# MCU_-_IMU.net
KiCad netlist of a schematic drawn in Altium Designer
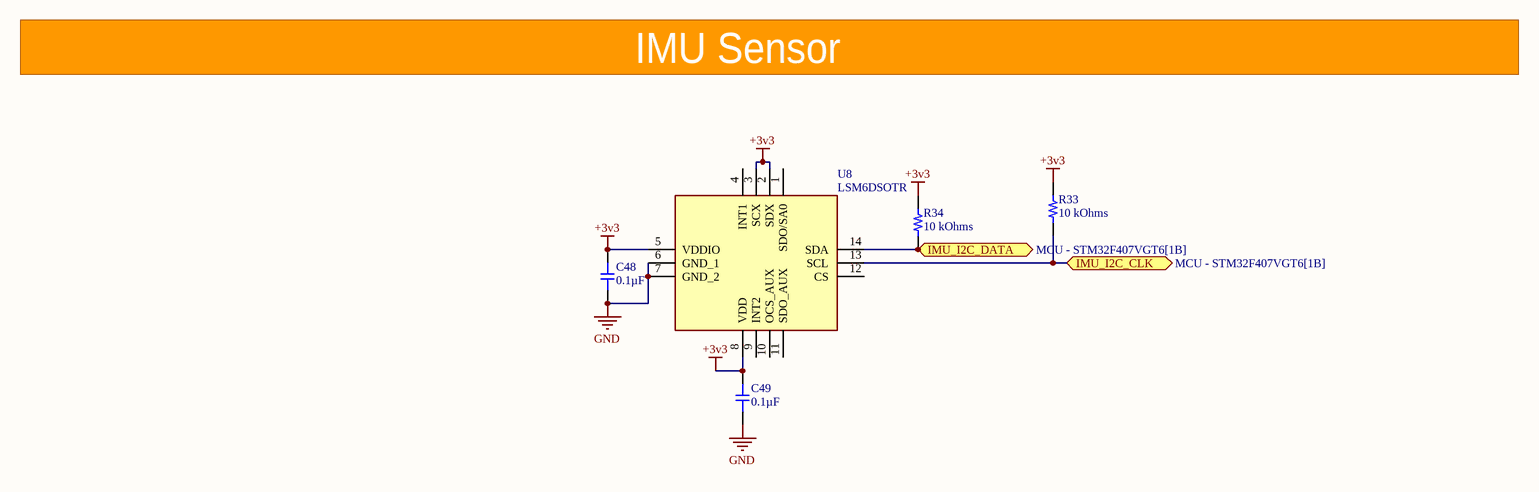
[diagram p0: MCU - IMU.SchDoc]

(export (version "E")
  (design (tool "Eeschema 10.0.6"))
  (components
    (comp (ref "C48")
      (value "0.1µF")
      (footprint "0603_Footprint")
      (description "0.1uF 0603 Surface Capacitor")
      (libsource (lib "ELK_H7-V2 Library") (part "0.1uF 0603 Surface Capacitor_1_1_1_1_1_1"))
    )
    (comp (ref "C49")
      (value "0.1µF")
      (footprint "0603_Footprint")
      (description "0.1uF 0603 Surface Capacitor")
      (libsource (lib "ELK_H7-V2 Library") (part "0.1uF 0603 Surface Capacitor_1_1_1_1_1_1"))
    )
    (comp (ref "R33")
      (value "10 kOhms")
      (footprint "0603_RES")
      (description "10 kOhms 0603")
      (libsource (lib "ELK_H7-V2 Library") (part "10 kOhms 0603"))
    )
    (comp (ref "R34")
      (value "10 kOhms")
      (footprint "0603_RES")
      (description "10 kOhms 0603")
      (libsource (lib "ELK_H7-V2 Library") (part "10 kOhms 0603"))
    )
    (comp (ref "U8")
      (value "LSM6DSOTR")
      (footprint "LGA-14(2.5X3X0.86)")
      (description "Accelerometer")
      (fields (field (name "MOUSER PART NUMBER") "511-LSM6DSOTR"))
      (libsource (lib "ELK_H7-V2 Library") (part "LSM6DSOTR"))
    )
  )
  (nets
    (net (code "1") (name "+3v3") (class "Default")
      (node (ref "C48") (pin "1") (pinfunction "1_1") (pintype "passive"))
      (node (ref "C49") (pin "1") (pinfunction "1_1") (pintype "passive"))
      (node (ref "R33") (pin "1") (pinfunction "1_1") (pintype "passive"))
      (node (ref "R34") (pin "2") (pinfunction "2_2") (pintype "passive"))
      (node (ref "U8") (pin "2") (pinfunction "SDX_2") (pintype "passive"))
      (node (ref "U8") (pin "3") (pinfunction "SCX_3") (pintype "passive"))
      (node (ref "U8") (pin "5") (pinfunction "VDDIO_5") (pintype "passive"))
      (node (ref "U8") (pin "8") (pinfunction "VDD_8") (pintype "passive"))
    )
    (net (code "2") (name "/IMU_I2C_CLK") (class "Default")
      (node (ref "R33") (pin "2") (pinfunction "2_2") (pintype "passive"))
      (node (ref "U8") (pin "13") (pinfunction "SCL_13") (pintype "passive"))
    )
    (net (code "3") (name "/IMU_I2C_DATA") (class "Default")
      (node (ref "R34") (pin "1") (pinfunction "1_1") (pintype "passive"))
      (node (ref "U8") (pin "14") (pinfunction "SDA_14") (pintype "passive"))
    )
    (net (code "4") (name "GND") (class "Default")
      (node (ref "C48") (pin "2") (pinfunction "2_2") (pintype "passive"))
      (node (ref "C49") (pin "2") (pinfunction "2_2") (pintype "passive"))
      (node (ref "U8") (pin "6") (pinfunction "GND_1_6") (pintype "passive"))
      (node (ref "U8") (pin "7") (pinfunction "GND_2_7") (pintype "passive"))
    )
    (net (code "5") (name "unconnected-(U8-CS-Pad12)") (class "Default")
      (node (ref "U8") (pin "12") (pinfunction "CS_12") (pintype "passive"))
    )
    (net (code "6") (name "unconnected-(U8-INT1-Pad4)") (class "Default")
      (node (ref "U8") (pin "4") (pinfunction "INT1_4") (pintype "passive"))
    )
    (net (code "7") (name "unconnected-(U8-INT2-Pad9)") (class "Default")
      (node (ref "U8") (pin "9") (pinfunction "INT2_9") (pintype "passive"))
    )
    (net (code "8") (name "unconnected-(U8-OCS_AUX-Pad10)") (class "Default")
      (node (ref "U8") (pin "10") (pinfunction "OCS_AUX_10") (pintype "passive"))
    )
    (net (code "9") (name "unconnected-(U8-SDO_AUX-Pad11)") (class "Default")
      (node (ref "U8") (pin "11") (pinfunction "SDO_AUX_11") (pintype "passive"))
    )
    (net (code "10") (name "unconnected-(U8-SDO{slash}SA0-Pad1)") (class "Default")
      (node (ref "U8") (pin "1") (pinfunction "SDO/SA0_1") (pintype "passive"))
    )
  )
)
